# Esquema.net
KiCad netlist of a schematic drawn in EAGLE
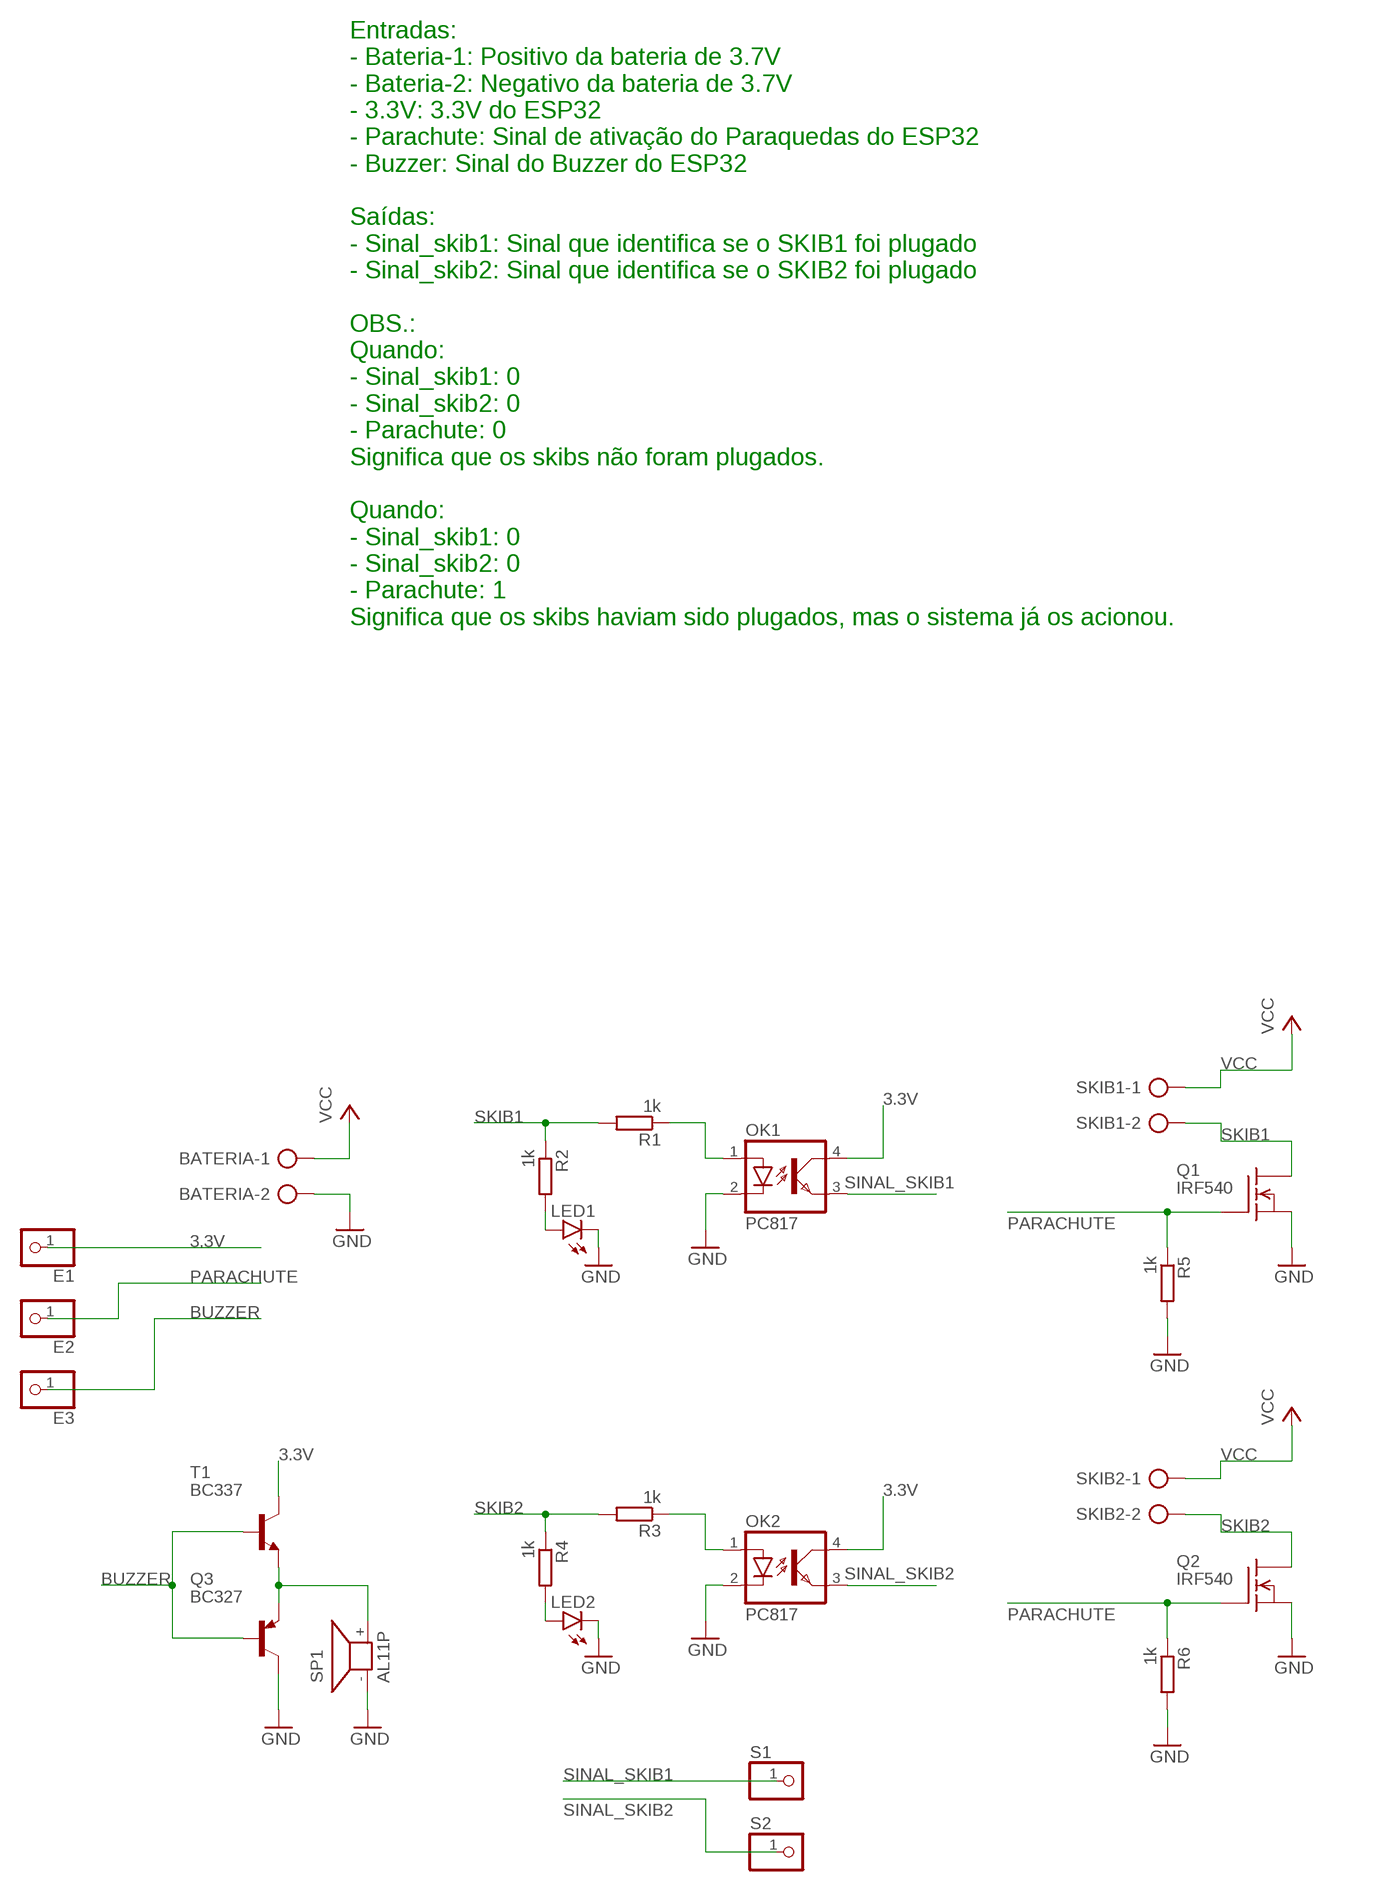
[diagram p0: schematic, sheet 1]

(export (version "E")
  (design (tool "Eeschema 10.0.6"))
  (components
    (comp (ref "BATERIA")
      (value "AK500/2-H")
      (footprint "eagle-import:AK500_2-H")
      (libsource (lib "eagle-import") (part "AK500/2-H"))
    )
    (comp (ref "E1")
      (value "PINHD-1X1")
      (footprint "eagle-import:1X01")
      (libsource (lib "eagle-import") (part "PINHD-1X1"))
    )
    (comp (ref "E2")
      (value "PINHD-1X1")
      (footprint "eagle-import:1X01")
      (libsource (lib "eagle-import") (part "PINHD-1X1"))
    )
    (comp (ref "E3")
      (value "PINHD-1X1")
      (footprint "eagle-import:1X01")
      (libsource (lib "eagle-import") (part "PINHD-1X1"))
    )
    (comp (ref "LED1")
      (value "LED5MM")
      (footprint "eagle-import:LED5MM")
      (libsource (lib "eagle-import") (part "LED5MM"))
    )
    (comp (ref "LED2")
      (value "LED5MM")
      (footprint "eagle-import:LED5MM")
      (libsource (lib "eagle-import") (part "LED5MM"))
    )
    (comp (ref "OK1")
      (value "PC817")
      (footprint "eagle-import:DIL04")
      (fields (field (name "MPN") "PC817X4J000F"))
      (libsource (lib "eagle-import") (part "PC817"))
    )
    (comp (ref "OK2")
      (value "PC817")
      (footprint "eagle-import:DIL04")
      (fields (field (name "MPN") "PC817X4J000F"))
      (libsource (lib "eagle-import") (part "PC817"))
    )
    (comp (ref "Q1")
      (value "IRF540")
      (footprint "eagle-import:TO220")
      (libsource (lib "eagle-import") (part "IRF540"))
    )
    (comp (ref "Q2")
      (value "IRF540")
      (footprint "eagle-import:TO220")
      (libsource (lib "eagle-import") (part "IRF540"))
    )
    (comp (ref "Q3")
      (value "BC327")
      (footprint "eagle-import:TO92")
      (libsource (lib "eagle-import") (part "BC327"))
    )
    (comp (ref "R1")
      (value "1k")
      (footprint "eagle-import:0207_10")
      (libsource (lib "eagle-import") (part "R-EU_0207/10"))
    )
    (comp (ref "R2")
      (value "1k")
      (footprint "eagle-import:0207_10")
      (libsource (lib "eagle-import") (part "R-EU_0207/10"))
    )
    (comp (ref "R3")
      (value "1k")
      (footprint "eagle-import:0207_10")
      (libsource (lib "eagle-import") (part "R-EU_0207/10"))
    )
    (comp (ref "R4")
      (value "1k")
      (footprint "eagle-import:0207_10")
      (libsource (lib "eagle-import") (part "R-EU_0207/10"))
    )
    (comp (ref "R5")
      (value "1k")
      (footprint "eagle-import:0207_10")
      (libsource (lib "eagle-import") (part "R-EU_0207/10"))
    )
    (comp (ref "R6")
      (value "1k")
      (footprint "eagle-import:0207_10")
      (libsource (lib "eagle-import") (part "R-EU_0207/10"))
    )
    (comp (ref "S1")
      (value "PINHD-1X1")
      (footprint "eagle-import:1X01")
      (libsource (lib "eagle-import") (part "PINHD-1X1"))
    )
    (comp (ref "S2")
      (value "PINHD-1X1")
      (footprint "eagle-import:1X01")
      (libsource (lib "eagle-import") (part "PINHD-1X1"))
    )
    (comp (ref "SKIB1")
      (value "AK500/2-H")
      (footprint "eagle-import:AK500_2-H")
      (libsource (lib "eagle-import") (part "AK500/2-H"))
    )
    (comp (ref "SKIB2")
      (value "AK500/2-H")
      (footprint "eagle-import:AK500_2-H")
      (libsource (lib "eagle-import") (part "AK500/2-H"))
    )
    (comp (ref "SP1")
      (value "AL11P")
      (footprint "eagle-import:AL11P")
      (libsource (lib "eagle-import") (part "AL11P"))
    )
    (comp (ref "T1")
      (value "BC337")
      (footprint "eagle-import:TO92")
      (libsource (lib "eagle-import") (part "BC337"))
    )
  )
  (nets
    (net (code "1") (name "/3.3V") (class "Default")
      (node (ref "E1") (pin "1") (pinfunction "1_1") (pintype "passive"))
      (node (ref "OK1") (pin "4") (pinfunction "COL_4") (pintype "passive"))
      (node (ref "OK2") (pin "4") (pinfunction "COL_4") (pintype "passive"))
      (node (ref "T1") (pin "3") (pinfunction "C_3") (pintype "passive"))
    )
    (net (code "2") (name "/BUZZER") (class "Default")
      (node (ref "E3") (pin "1") (pinfunction "1_1") (pintype "passive"))
      (node (ref "Q3") (pin "2") (pinfunction "B_2") (pintype "passive"))
      (node (ref "T1") (pin "2") (pinfunction "B_2") (pintype "passive"))
    )
    (net (code "3") (name "/PARACHUTE") (class "Default")
      (node (ref "E2") (pin "1") (pinfunction "1_1") (pintype "passive"))
      (node (ref "Q1") (pin "1") (pinfunction "G_1") (pintype "passive"))
      (node (ref "Q2") (pin "1") (pinfunction "G_1") (pintype "passive"))
      (node (ref "R5") (pin "1") (pinfunction "1_1") (pintype "passive"))
      (node (ref "R6") (pin "1") (pinfunction "1_1") (pintype "passive"))
    )
    (net (code "4") (name "/SINAL_SKIB1") (class "Default")
      (node (ref "OK1") (pin "3") (pinfunction "EMIT_3") (pintype "passive"))
      (node (ref "S1") (pin "1") (pinfunction "1_1") (pintype "passive"))
    )
    (net (code "5") (name "/SINAL_SKIB2") (class "Default")
      (node (ref "OK2") (pin "3") (pinfunction "EMIT_3") (pintype "passive"))
      (node (ref "S2") (pin "1") (pinfunction "1_1") (pintype "passive"))
    )
    (net (code "6") (name "/SKIB1") (class "Default")
      (node (ref "Q1") (pin "2") (pinfunction "D_2") (pintype "passive"))
      (node (ref "R1") (pin "2") (pinfunction "2_2") (pintype "passive"))
      (node (ref "R2") (pin "1") (pinfunction "1_1") (pintype "passive"))
      (node (ref "SKIB1") (pin "2") (pinfunction "KL_2") (pintype "passive"))
    )
    (net (code "7") (name "/SKIB2") (class "Default")
      (node (ref "Q2") (pin "2") (pinfunction "D_2") (pintype "passive"))
      (node (ref "R3") (pin "2") (pinfunction "2_2") (pintype "passive"))
      (node (ref "R4") (pin "1") (pinfunction "1_1") (pintype "passive"))
      (node (ref "SKIB2") (pin "2") (pinfunction "KL_2") (pintype "passive"))
    )
    (net (code "8") (name "GND") (class "Default")
      (node (ref "BATERIA") (pin "2") (pinfunction "KL_2") (pintype "passive"))
      (node (ref "LED1") (pin "K") (pinfunction "C_K") (pintype "passive"))
      (node (ref "LED2") (pin "K") (pinfunction "C_K") (pintype "passive"))
      (node (ref "OK1") (pin "2") (pinfunction "C_2") (pintype "passive"))
      (node (ref "OK2") (pin "2") (pinfunction "C_2") (pintype "passive"))
      (node (ref "Q1") (pin "3") (pinfunction "S_3") (pintype "passive"))
      (node (ref "Q2") (pin "3") (pinfunction "S_3") (pintype "passive"))
      (node (ref "Q3") (pin "3") (pinfunction "C_3") (pintype "passive"))
      (node (ref "R5") (pin "2") (pinfunction "2_2") (pintype "passive"))
      (node (ref "R6") (pin "2") (pinfunction "2_2") (pintype "passive"))
      (node (ref "SP1") (pin "-") (pinfunction "1_-") (pintype "passive"))
    )
    (net (code "9") (name "Net-(LED1-PadA)") (class "Default")
      (node (ref "LED1") (pin "A") (pinfunction "A_A") (pintype "passive"))
      (node (ref "R2") (pin "2") (pinfunction "2_2") (pintype "passive"))
    )
    (net (code "10") (name "Net-(LED2-PadA)") (class "Default")
      (node (ref "LED2") (pin "A") (pinfunction "A_A") (pintype "passive"))
      (node (ref "R4") (pin "2") (pinfunction "2_2") (pintype "passive"))
    )
    (net (code "11") (name "Net-(OK1-A)") (class "Default")
      (node (ref "OK1") (pin "1") (pinfunction "A_1") (pintype "passive"))
      (node (ref "R1") (pin "1") (pinfunction "1_1") (pintype "passive"))
    )
    (net (code "12") (name "Net-(OK2-A)") (class "Default")
      (node (ref "OK2") (pin "1") (pinfunction "A_1") (pintype "passive"))
      (node (ref "R3") (pin "1") (pinfunction "1_1") (pintype "passive"))
    )
    (net (code "13") (name "Net-(Q3-E)") (class "Default")
      (node (ref "Q3") (pin "1") (pinfunction "E_1") (pintype "passive"))
      (node (ref "SP1") (pin "+") (pinfunction "2_+") (pintype "passive"))
      (node (ref "T1") (pin "1") (pinfunction "E_1") (pintype "passive"))
    )
    (net (code "14") (name "VCC") (class "Default")
      (node (ref "BATERIA") (pin "1") (pinfunction "KL_1") (pintype "passive"))
      (node (ref "SKIB1") (pin "1") (pinfunction "KL_1") (pintype "passive"))
      (node (ref "SKIB2") (pin "1") (pinfunction "KL_1") (pintype "passive"))
    )
  )
)
